# Herfstkamp_v1.net
KiCad netlist of a schematic drawn in EAGLE
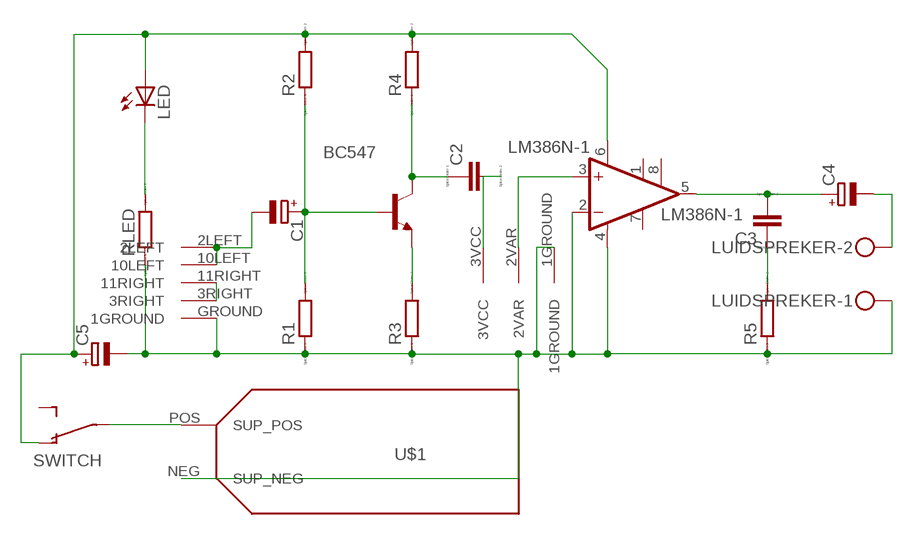
[diagram p0: schematic, sheet 1]

(export (version "E")
  (design (tool "Eeschema 10.0.6"))
  (components
    (comp (ref "BC547")
      (value "-NPN-TO92-CBE")
      (footprint "eagle-import:TO92-CBE")
      (libsource (lib "eagle-import") (part "-NPN-TO92-CBE"))
    )
    (comp (ref "C1")
      (value "CPOL-EUE2-5")
      (footprint "eagle-import:E2-5")
      (libsource (lib "eagle-import") (part "CPOL-EUE2-5"))
    )
    (comp (ref "C2")
      (value "C-EU050-024X044")
      (footprint "eagle-import:C050-024X044")
      (libsource (lib "eagle-import") (part "C-EU050-024X044"))
    )
    (comp (ref "C3")
      (value "C-EU050-024X044")
      (footprint "eagle-import:C050-024X044")
      (libsource (lib "eagle-import") (part "C-EU050-024X044"))
    )
    (comp (ref "C4")
      (value "CPOL-EUE2.5-6")
      (footprint "eagle-import:E2,5-6")
      (libsource (lib "eagle-import") (part "CPOL-EUE2.5-6"))
    )
    (comp (ref "C5")
      (value "CPOL-EUE3.5-8")
      (footprint "eagle-import:E3,5-8")
      (libsource (lib "eagle-import") (part "CPOL-EUE3.5-8"))
    )
    (comp (ref "LED")
      (value "LED5MM")
      (footprint "eagle-import:LED5MM")
      (libsource (lib "eagle-import") (part "LED5MM"))
    )
    (comp (ref "LM386N-1")
      (value "LM386N-1")
      (footprint "eagle-import:DIL08")
      (libsource (lib "eagle-import") (part "LM386?-N1"))
    )
    (comp (ref "LUIDSPREKER")
      (value "MKDSN1,5/2-5,08")
      (footprint "eagle-import:MKDSN1,5_2-5,08")
      (libsource (lib "eagle-import") (part "MKDSN1,5/2-5,08"))
    )
    (comp (ref "POTENTIOMETER")
      (value "POTENTIOMETERALPS")
      (footprint "eagle-import:POTENTIOMETERALPS")
      (libsource (lib "eagle-import") (part "POTENTIOMETERALPS"))
    )
    (comp (ref "R1")
      (value "R-EU_0207_10")
      (footprint "eagle-import:0207_10")
      (libsource (lib "eagle-import") (part "R-EU_0207_10"))
    )
    (comp (ref "R2")
      (value "R-EU_0207_10")
      (footprint "eagle-import:0207_10")
      (libsource (lib "eagle-import") (part "R-EU_0207_10"))
    )
    (comp (ref "R3")
      (value "R-EU_0207_10")
      (footprint "eagle-import:0207_10")
      (libsource (lib "eagle-import") (part "R-EU_0207_10"))
    )
    (comp (ref "R4")
      (value "R-EU_0207_10")
      (footprint "eagle-import:0207_10")
      (libsource (lib "eagle-import") (part "R-EU_0207_10"))
    )
    (comp (ref "R5")
      (value "R-EU_0207_10")
      (footprint "eagle-import:0207_10")
      (libsource (lib "eagle-import") (part "R-EU_0207_10"))
    )
    (comp (ref "RLED")
      (value "R-EU_0207_10")
      (footprint "eagle-import:0207_10")
      (libsource (lib "eagle-import") (part "R-EU_0207_10"))
    )
    (comp (ref "SWITCH")
      (value "SPDT_OS102011MAQN1")
      (footprint "eagle-import:OS102011MA1Q")
      (libsource (lib "eagle-import") (part "SPDT_OS102011MAQN1"))
    )
    (comp (ref "U$1")
      (value "BATTERY_HOLDER9V")
      (footprint "eagle-import:BAT_HOLDER_9V")
      (libsource (lib "eagle-import") (part "BATTERY_HOLDER9V"))
    )
    (comp (ref "U$2")
      (value "INPUTJACK")
      (footprint "eagle-import:JACKSOCKET35RAPC4BHN2")
      (libsource (lib "eagle-import") (part "INPUTJACK"))
    )
  )
  (nets
    (net (code "1") (name "Net-(BC547-PadB)") (class "Default")
      (node (ref "BC547") (pin "B") (pinfunction "B_B") (pintype "passive"))
      (node (ref "C1") (pin "+") (pinfunction "+_+") (pintype "passive"))
      (node (ref "R1") (pin "2") (pinfunction "2_2") (pintype "passive"))
      (node (ref "R2") (pin "1") (pinfunction "1_1") (pintype "passive"))
    )
    (net (code "2") (name "Net-(BC547-PadC)") (class "Default")
      (node (ref "BC547") (pin "C") (pinfunction "C_C") (pintype "passive"))
      (node (ref "C2") (pin "1") (pinfunction "1_1") (pintype "passive"))
      (node (ref "R4") (pin "1") (pinfunction "1_1") (pintype "passive"))
    )
    (net (code "3") (name "Net-(BC547-PadE)") (class "Default")
      (node (ref "BC547") (pin "E") (pinfunction "E_E") (pintype "passive"))
      (node (ref "R3") (pin "2") (pinfunction "2_2") (pintype "passive"))
    )
    (net (code "4") (name "Net-(C1-Pad-)") (class "Default")
      (node (ref "C1") (pin "-") (pinfunction "-_-") (pintype "passive"))
      (node (ref "U$2") (pin "10LEFT") (pinfunction "10LEFT_10LEFT") (pintype "bidirectional"))
      (node (ref "U$2") (pin "2LEFT") (pinfunction "2LEFT_2LEFT") (pintype "bidirectional"))
    )
    (net (code "5") (name "Net-(C2-Pad2)") (class "Default")
      (node (ref "C2") (pin "2") (pinfunction "2_2") (pintype "passive"))
      (node (ref "POTENTIOMETER") (pin "3VCC") (pinfunction "3VCC_3VCC") (pintype "bidirectional"))
    )
    (net (code "6") (name "Net-(C3-Pad1)") (class "Default")
      (node (ref "C3") (pin "1") (pinfunction "1_1") (pintype "passive"))
      (node (ref "R5") (pin "2") (pinfunction "2_2") (pintype "passive"))
    )
    (net (code "7") (name "Net-(LED-C)") (class "Default")
      (node (ref "LED") (pin "K") (pinfunction "C_K") (pintype "passive"))
      (node (ref "RLED") (pin "2") (pinfunction "2_2") (pintype "passive"))
    )
    (net (code "8") (name "Net-(LM386N-1-+IN)") (class "Default")
      (node (ref "LM386N-1") (pin "3") (pinfunction "+IN_3") (pintype "input"))
      (node (ref "POTENTIOMETER") (pin "2VAR") (pinfunction "2VAR_2VAR") (pintype "bidirectional"))
    )
    (net (code "9") (name "Net-(LM386N-1--IN)") (class "Default")
      (node (ref "C5") (pin "-") (pinfunction "-_-") (pintype "passive"))
      (node (ref "LM386N-1") (pin "2") (pinfunction "-IN_2") (pintype "input"))
      (node (ref "LM386N-1") (pin "4") (pinfunction "GND_4") (pintype "power_in"))
      (node (ref "LUIDSPREKER") (pin "1") (pinfunction "KL_1") (pintype "passive"))
      (node (ref "POTENTIOMETER") (pin "1GROUND") (pinfunction "1GROUND_1GROUND") (pintype "bidirectional"))
      (node (ref "R1") (pin "1") (pinfunction "1_1") (pintype "passive"))
      (node (ref "R3") (pin "1") (pinfunction "1_1") (pintype "passive"))
      (node (ref "R5") (pin "1") (pinfunction "1_1") (pintype "passive"))
      (node (ref "RLED") (pin "1") (pinfunction "1_1") (pintype "passive"))
      (node (ref "U$1") (pin "NEG") (pinfunction "SUP_NEG_NEG") (pintype "bidirectional"))
      (node (ref "U$2") (pin "GROUND") (pinfunction "1GROUND_GROUND") (pintype "bidirectional"))
    )
    (net (code "10") (name "Net-(LM386N-1-OUT)") (class "Default")
      (node (ref "C3") (pin "2") (pinfunction "2_2") (pintype "passive"))
      (node (ref "C4") (pin "+") (pinfunction "+_+") (pintype "passive"))
      (node (ref "LM386N-1") (pin "5") (pinfunction "OUT_5") (pintype "output"))
    )
    (net (code "11") (name "Net-(LM386N-1-VS)") (class "Default")
      (node (ref "C5") (pin "+") (pinfunction "+_+") (pintype "passive"))
      (node (ref "LED") (pin "A") (pinfunction "A_A") (pintype "passive"))
      (node (ref "LM386N-1") (pin "6") (pinfunction "VS_6") (pintype "power_in"))
      (node (ref "R2") (pin "2") (pinfunction "2_2") (pintype "passive"))
      (node (ref "R4") (pin "2") (pinfunction "2_2") (pintype "passive"))
      (node (ref "SWITCH") (pin "P$1") (pinfunction "O1_P$1") (pintype "passive"))
    )
    (net (code "12") (name "Net-(LUIDSPREKERB-KL)") (class "Default")
      (node (ref "C4") (pin "-") (pinfunction "-_-") (pintype "passive"))
      (node (ref "LUIDSPREKER") (pin "2") (pinfunction "KL_2") (pintype "passive"))
    )
    (net (code "13") (name "Net-(SWITCH-P)") (class "Default")
      (node (ref "SWITCH") (pin "P$2") (pinfunction "P_P$2") (pintype "passive"))
      (node (ref "U$1") (pin "POS") (pinfunction "SUP_POS_POS") (pintype "bidirectional"))
    )
    (net (code "14") (name "Net-(U$2-Pad11RIGHT)") (class "Default")
      (node (ref "U$2") (pin "11RIGHT") (pinfunction "11RIGHT_11RIGHT") (pintype "bidirectional"))
      (node (ref "U$2") (pin "3RIGHT") (pinfunction "3RIGHT_3RIGHT") (pintype "bidirectional"))
    )
    (net (code "15") (name "unconnected-(LM386N-1-BYPASS-Pad7)") (class "Default")
      (node (ref "LM386N-1") (pin "7") (pinfunction "BYPASS_7") (pintype "passive"))
    )
    (net (code "16") (name "unconnected-(LM386N-1-GAIN-Pad1)") (class "Default")
      (node (ref "LM386N-1") (pin "1") (pinfunction "GAIN_1") (pintype "passive"))
    )
    (net (code "17") (name "unconnected-(LM386N-1-GAIN-Pad8)") (class "Default")
      (node (ref "LM386N-1") (pin "8") (pinfunction "GAIN_8") (pintype "passive"))
    )
    (net (code "18") (name "unconnected-(SWITCH-O2-PadP$3)") (class "Default")
      (node (ref "SWITCH") (pin "P$3") (pinfunction "O2_P$3") (pintype "passive"))
    )
  )
)
